# IO_BOARD_BOTTOM.net
KiCad netlist of a schematic drawn in EAGLE
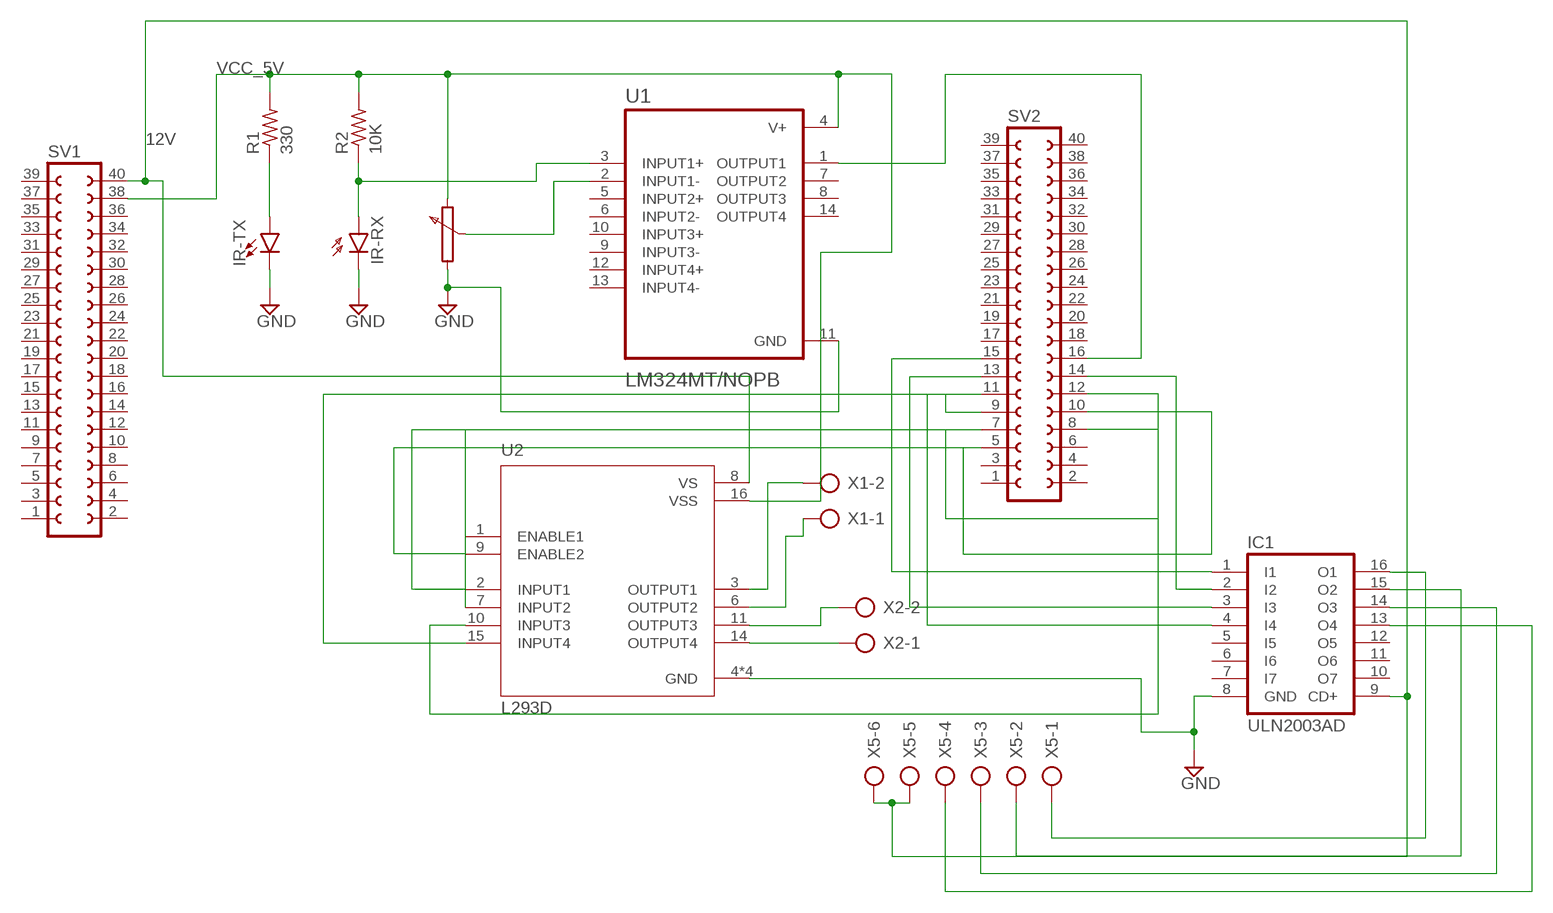
[diagram p0: schematic, sheet 1]

(export (version "E")
  (design (tool "Eeschema 10.0.6"))
  (components
    (comp (ref "IC1")
      (value "ULN2003AD")
      (footprint "eagle-import:SO16")
      (fields (field (name "MF") "STMicroelectronics") (field (name "MP") "ULN2003A"))
      (libsource (lib "eagle-import") (part "ULN2003AD"))
    )
    (comp (ref "IR-RX")
      (value "SFH205")
      (footprint "eagle-import:SFH205")
      (libsource (lib "eagle-import") (part "SFH205"))
    )
    (comp (ref "IR-TX")
      (value "LED-IRTSAL6100")
      (footprint "eagle-import:LED_5MM")
      (libsource (lib "eagle-import") (part "LED-IRTSAL6100"))
    )
    (comp (ref "R1")
      (value "330")
      (footprint "eagle-import:0204V")
      (libsource (lib "eagle-import") (part "R-US_0204/2V"))
    )
    (comp (ref "R2")
      (value "10K")
      (footprint "eagle-import:0204V")
      (libsource (lib "eagle-import") (part "R-US_0204/2V"))
    )
    (comp (ref "SV1")
      (value "FE20-2")
      (footprint "eagle-import:FE20-2")
      (libsource (lib "eagle-import") (part "FE20-2"))
    )
    (comp (ref "SV2")
      (value "FE20-2")
      (footprint "eagle-import:FE20-2")
      (libsource (lib "eagle-import") (part "FE20-2"))
    )
    (comp (ref "U1")
      (value "LM324MT/NOPB")
      (footprint "eagle-import:SOP65P640X120-14N")
      (fields (field (name "MF") "Texas Instruments") (field (name "MP") "LM324MT"))
      (libsource (lib "eagle-import") (part "LM324MT/NOPB"))
    )
    (comp (ref "U2")
      (value "L293D")
      (footprint "eagle-import:DIP880W50P254L2000H510Q16")
      (fields (field (name "MF") "STMicroelectronics"))
      (libsource (lib "eagle-import") (part "L293D"))
    )
    (comp (ref "X1")
      (value "AK500/2")
      (footprint "eagle-import:AK500_2")
      (libsource (lib "eagle-import") (part "AK500/2"))
    )
    (comp (ref "X2")
      (value "AK500/2")
      (footprint "eagle-import:AK500_2")
      (libsource (lib "eagle-import") (part "AK500/2"))
    )
    (comp (ref "X5")
      (value "AK500/6")
      (footprint "eagle-import:AK500_6")
      (libsource (lib "eagle-import") (part "AK500/6"))
    )
  )
  (nets
    (net (code "1") (name "/12V") (class "Default")
      (node (ref "IC1") (pin "9") (pinfunction "CD+_9") (pintype "passive"))
      (node (ref "SV1") (pin "40") (pinfunction "40_40") (pintype "passive"))
      (node (ref "U2") (pin "8") (pinfunction "VS_8") (pintype "power_in"))
      (node (ref "X5") (pin "5") (pinfunction "KL_5") (pintype "passive"))
      (node (ref "X5") (pin "6") (pinfunction "KL_6") (pintype "passive"))
    )
    (net (code "2") (name "/VCC_5V") (class "Default")
      (node (ref "R1") (pin "2") (pinfunction "2_2") (pintype "passive"))
      (node (ref "R2") (pin "2") (pinfunction "2_2") (pintype "passive"))
      (node (ref "SV1") (pin "38") (pinfunction "38_38") (pintype "passive"))
      (node (ref "U1") (pin "4") (pinfunction "V+_4") (pintype "power_in"))
      (node (ref "U2") (pin "16") (pinfunction "VSS_16") (pintype "power_in"))
    )
    (net (code "3") (name "GND") (class "Default")
      (node (ref "IC1") (pin "8") (pinfunction "GND_8") (pintype "power_in"))
      (node (ref "IR-RX") (pin "K") (pinfunction "C_K") (pintype "passive"))
      (node (ref "IR-TX") (pin "K") (pinfunction "C_K") (pintype "passive"))
      (node (ref "U1") (pin "11") (pinfunction "GND_11") (pintype "power_in"))
      (node (ref "U2") (pin "12") (pinfunction "GND_12") (pintype "power_in"))
      (node (ref "U2") (pin "13") (pinfunction "GND_13") (pintype "power_in"))
      (node (ref "U2") (pin "4") (pinfunction "GND_4") (pintype "power_in"))
      (node (ref "U2") (pin "5") (pinfunction "GND_5") (pintype "power_in"))
    )
    (net (code "4") (name "Net-(IC1-I1)") (class "Default")
      (node (ref "IC1") (pin "1") (pinfunction "I1_1") (pintype "input"))
      (node (ref "SV2") (pin "15") (pinfunction "15_15") (pintype "passive"))
    )
    (net (code "5") (name "Net-(IC1-I2)") (class "Default")
      (node (ref "IC1") (pin "2") (pinfunction "I2_2") (pintype "input"))
      (node (ref "SV2") (pin "14") (pinfunction "14_14") (pintype "passive"))
    )
    (net (code "6") (name "Net-(IC1-I3)") (class "Default")
      (node (ref "IC1") (pin "3") (pinfunction "I3_3") (pintype "input"))
      (node (ref "SV2") (pin "13") (pinfunction "13_13") (pintype "passive"))
    )
    (net (code "7") (name "Net-(IC1-I4)") (class "Default")
      (node (ref "IC1") (pin "4") (pinfunction "I4_4") (pintype "input"))
      (node (ref "SV2") (pin "11") (pinfunction "11_11") (pintype "passive"))
    )
    (net (code "8") (name "Net-(IC1-O1)") (class "Default")
      (node (ref "IC1") (pin "16") (pinfunction "O1_16") (pintype "open_collector"))
      (node (ref "X5") (pin "1") (pinfunction "KL_1") (pintype "passive"))
    )
    (net (code "9") (name "Net-(IC1-O2)") (class "Default")
      (node (ref "IC1") (pin "15") (pinfunction "O2_15") (pintype "open_collector"))
      (node (ref "X5") (pin "2") (pinfunction "KL_2") (pintype "passive"))
    )
    (net (code "10") (name "Net-(IC1-O3)") (class "Default")
      (node (ref "IC1") (pin "14") (pinfunction "O3_14") (pintype "open_collector"))
      (node (ref "X5") (pin "3") (pinfunction "KL_3") (pintype "passive"))
    )
    (net (code "11") (name "Net-(IC1-O4)") (class "Default")
      (node (ref "IC1") (pin "13") (pinfunction "O4_13") (pintype "open_collector"))
      (node (ref "X5") (pin "4") (pinfunction "KL_4") (pintype "passive"))
    )
    (net (code "12") (name "Net-(IR-TX-PadA)") (class "Default")
      (node (ref "IR-TX") (pin "A") (pinfunction "A_A") (pintype "passive"))
      (node (ref "R1") (pin "1") (pinfunction "1_1") (pintype "passive"))
    )
    (net (code "13") (name "Net-(U1-INPUT1+)") (class "Default")
      (node (ref "IR-RX") (pin "A") (pinfunction "A_A") (pintype "passive"))
      (node (ref "R2") (pin "1") (pinfunction "1_1") (pintype "passive"))
      (node (ref "U1") (pin "3") (pinfunction "INPUT1+_3") (pintype "input"))
    )
    (net (code "14") (name "Net-(U1-OUTPUT1)") (class "Default")
      (node (ref "SV2") (pin "16") (pinfunction "16_16") (pintype "passive"))
      (node (ref "U1") (pin "1") (pinfunction "OUTPUT1_1") (pintype "output"))
    )
    (net (code "15") (name "Net-(U2-ENABLE1)") (class "Default")
      (node (ref "SV2") (pin "8") (pinfunction "8_8") (pintype "passive"))
      (node (ref "U2") (pin "1") (pinfunction "ENABLE1_1") (pintype "input"))
    )
    (net (code "16") (name "Net-(U2-ENABLE2)") (class "Default")
      (node (ref "SV2") (pin "10") (pinfunction "10_10") (pintype "passive"))
      (node (ref "U2") (pin "9") (pinfunction "ENABLE2_9") (pintype "input"))
    )
    (net (code "17") (name "Net-(U2-INPUT1)") (class "Default")
      (node (ref "SV2") (pin "7") (pinfunction "7_7") (pintype "passive"))
      (node (ref "U2") (pin "2") (pinfunction "INPUT1_2") (pintype "input"))
    )
    (net (code "18") (name "Net-(U2-INPUT2)") (class "Default")
      (node (ref "SV2") (pin "5") (pinfunction "5_5") (pintype "passive"))
      (node (ref "U2") (pin "7") (pinfunction "INPUT2_7") (pintype "input"))
    )
    (net (code "19") (name "Net-(U2-INPUT3)") (class "Default")
      (node (ref "SV2") (pin "12") (pinfunction "12_12") (pintype "passive"))
      (node (ref "U2") (pin "10") (pinfunction "INPUT3_10") (pintype "input"))
    )
    (net (code "20") (name "Net-(U2-INPUT4)") (class "Default")
      (node (ref "SV2") (pin "9") (pinfunction "9_9") (pintype "passive"))
      (node (ref "U2") (pin "15") (pinfunction "INPUT4_15") (pintype "input"))
    )
    (net (code "21") (name "Net-(U2-OUTPUT1)") (class "Default")
      (node (ref "U2") (pin "3") (pinfunction "OUTPUT1_3") (pintype "output"))
      (node (ref "X1") (pin "2") (pinfunction "KL_2") (pintype "passive"))
    )
    (net (code "22") (name "Net-(U2-OUTPUT2)") (class "Default")
      (node (ref "U2") (pin "6") (pinfunction "OUTPUT2_6") (pintype "output"))
      (node (ref "X1") (pin "1") (pinfunction "KL_1") (pintype "passive"))
    )
    (net (code "23") (name "Net-(U2-OUTPUT3)") (class "Default")
      (node (ref "U2") (pin "11") (pinfunction "OUTPUT3_11") (pintype "output"))
      (node (ref "X2") (pin "2") (pinfunction "KL_2") (pintype "passive"))
    )
    (net (code "24") (name "Net-(U2-OUTPUT4)") (class "Default")
      (node (ref "U2") (pin "14") (pinfunction "OUTPUT4_14") (pintype "output"))
      (node (ref "X2") (pin "1") (pinfunction "KL_1") (pintype "passive"))
    )
    (net (code "25") (name "unconnected-(IC1-I5-Pad5)") (class "Default")
      (node (ref "IC1") (pin "5") (pinfunction "I5_5") (pintype "input"))
    )
    (net (code "26") (name "unconnected-(IC1-I6-Pad6)") (class "Default")
      (node (ref "IC1") (pin "6") (pinfunction "I6_6") (pintype "input"))
    )
    (net (code "27") (name "unconnected-(IC1-I7-Pad7)") (class "Default")
      (node (ref "IC1") (pin "7") (pinfunction "I7_7") (pintype "input"))
    )
    (net (code "28") (name "unconnected-(IC1-O5-Pad12)") (class "Default")
      (node (ref "IC1") (pin "12") (pinfunction "O5_12") (pintype "open_collector"))
    )
    (net (code "29") (name "unconnected-(IC1-O6-Pad11)") (class "Default")
      (node (ref "IC1") (pin "11") (pinfunction "O6_11") (pintype "open_collector"))
    )
    (net (code "30") (name "unconnected-(IC1-O7-Pad10)") (class "Default")
      (node (ref "IC1") (pin "10") (pinfunction "O7_10") (pintype "open_collector"))
    )
    (net (code "31") (name "unconnected-(SV1-Pad1)") (class "Default")
      (node (ref "SV1") (pin "1") (pinfunction "1_1") (pintype "passive"))
    )
    (net (code "32") (name "unconnected-(SV1-Pad2)") (class "Default")
      (node (ref "SV1") (pin "2") (pinfunction "2_2") (pintype "passive"))
    )
    (net (code "33") (name "unconnected-(SV1-Pad3)") (class "Default")
      (node (ref "SV1") (pin "3") (pinfunction "3_3") (pintype "passive"))
    )
    (net (code "34") (name "unconnected-(SV1-Pad4)") (class "Default")
      (node (ref "SV1") (pin "4") (pinfunction "4_4") (pintype "passive"))
    )
    (net (code "35") (name "unconnected-(SV1-Pad5)") (class "Default")
      (node (ref "SV1") (pin "5") (pinfunction "5_5") (pintype "passive"))
    )
    (net (code "36") (name "unconnected-(SV1-Pad6)") (class "Default")
      (node (ref "SV1") (pin "6") (pinfunction "6_6") (pintype "passive"))
    )
    (net (code "37") (name "unconnected-(SV1-Pad7)") (class "Default")
      (node (ref "SV1") (pin "7") (pinfunction "7_7") (pintype "passive"))
    )
    (net (code "38") (name "unconnected-(SV1-Pad8)") (class "Default")
      (node (ref "SV1") (pin "8") (pinfunction "8_8") (pintype "passive"))
    )
    (net (code "39") (name "unconnected-(SV1-Pad9)") (class "Default")
      (node (ref "SV1") (pin "9") (pinfunction "9_9") (pintype "passive"))
    )
    (net (code "40") (name "unconnected-(SV1-Pad10)") (class "Default")
      (node (ref "SV1") (pin "10") (pinfunction "10_10") (pintype "passive"))
    )
    (net (code "41") (name "unconnected-(SV1-Pad11)") (class "Default")
      (node (ref "SV1") (pin "11") (pinfunction "11_11") (pintype "passive"))
    )
    (net (code "42") (name "unconnected-(SV1-Pad12)") (class "Default")
      (node (ref "SV1") (pin "12") (pinfunction "12_12") (pintype "passive"))
    )
    (net (code "43") (name "unconnected-(SV1-Pad13)") (class "Default")
      (node (ref "SV1") (pin "13") (pinfunction "13_13") (pintype "passive"))
    )
    (net (code "44") (name "unconnected-(SV1-Pad14)") (class "Default")
      (node (ref "SV1") (pin "14") (pinfunction "14_14") (pintype "passive"))
    )
    (net (code "45") (name "unconnected-(SV1-Pad15)") (class "Default")
      (node (ref "SV1") (pin "15") (pinfunction "15_15") (pintype "passive"))
    )
    (net (code "46") (name "unconnected-(SV1-Pad16)") (class "Default")
      (node (ref "SV1") (pin "16") (pinfunction "16_16") (pintype "passive"))
    )
    (net (code "47") (name "unconnected-(SV1-Pad17)") (class "Default")
      (node (ref "SV1") (pin "17") (pinfunction "17_17") (pintype "passive"))
    )
    (net (code "48") (name "unconnected-(SV1-Pad18)") (class "Default")
      (node (ref "SV1") (pin "18") (pinfunction "18_18") (pintype "passive"))
    )
    (net (code "49") (name "unconnected-(SV1-Pad19)") (class "Default")
      (node (ref "SV1") (pin "19") (pinfunction "19_19") (pintype "passive"))
    )
    (net (code "50") (name "unconnected-(SV1-Pad20)") (class "Default")
      (node (ref "SV1") (pin "20") (pinfunction "20_20") (pintype "passive"))
    )
    (net (code "51") (name "unconnected-(SV1-Pad21)") (class "Default")
      (node (ref "SV1") (pin "21") (pinfunction "21_21") (pintype "passive"))
    )
    (net (code "52") (name "unconnected-(SV1-Pad22)") (class "Default")
      (node (ref "SV1") (pin "22") (pinfunction "22_22") (pintype "passive"))
    )
    (net (code "53") (name "unconnected-(SV1-Pad23)") (class "Default")
      (node (ref "SV1") (pin "23") (pinfunction "23_23") (pintype "passive"))
    )
    (net (code "54") (name "unconnected-(SV1-Pad24)") (class "Default")
      (node (ref "SV1") (pin "24") (pinfunction "24_24") (pintype "passive"))
    )
    (net (code "55") (name "unconnected-(SV1-Pad25)") (class "Default")
      (node (ref "SV1") (pin "25") (pinfunction "25_25") (pintype "passive"))
    )
    (net (code "56") (name "unconnected-(SV1-Pad26)") (class "Default")
      (node (ref "SV1") (pin "26") (pinfunction "26_26") (pintype "passive"))
    )
    (net (code "57") (name "unconnected-(SV1-Pad27)") (class "Default")
      (node (ref "SV1") (pin "27") (pinfunction "27_27") (pintype "passive"))
    )
    (net (code "58") (name "unconnected-(SV1-Pad28)") (class "Default")
      (node (ref "SV1") (pin "28") (pinfunction "28_28") (pintype "passive"))
    )
    (net (code "59") (name "unconnected-(SV1-Pad29)") (class "Default")
      (node (ref "SV1") (pin "29") (pinfunction "29_29") (pintype "passive"))
    )
    (net (code "60") (name "unconnected-(SV1-Pad30)") (class "Default")
      (node (ref "SV1") (pin "30") (pinfunction "30_30") (pintype "passive"))
    )
    (net (code "61") (name "unconnected-(SV1-Pad31)") (class "Default")
      (node (ref "SV1") (pin "31") (pinfunction "31_31") (pintype "passive"))
    )
    (net (code "62") (name "unconnected-(SV1-Pad32)") (class "Default")
      (node (ref "SV1") (pin "32") (pinfunction "32_32") (pintype "passive"))
    )
    (net (code "63") (name "unconnected-(SV1-Pad33)") (class "Default")
      (node (ref "SV1") (pin "33") (pinfunction "33_33") (pintype "passive"))
    )
    (net (code "64") (name "unconnected-(SV1-Pad34)") (class "Default")
      (node (ref "SV1") (pin "34") (pinfunction "34_34") (pintype "passive"))
    )
    (net (code "65") (name "unconnected-(SV1-Pad35)") (class "Default")
      (node (ref "SV1") (pin "35") (pinfunction "35_35") (pintype "passive"))
    )
    (net (code "66") (name "unconnected-(SV1-Pad36)") (class "Default")
      (node (ref "SV1") (pin "36") (pinfunction "36_36") (pintype "passive"))
    )
    (net (code "67") (name "unconnected-(SV1-Pad37)") (class "Default")
      (node (ref "SV1") (pin "37") (pinfunction "37_37") (pintype "passive"))
    )
    (net (code "68") (name "unconnected-(SV1-Pad39)") (class "Default")
      (node (ref "SV1") (pin "39") (pinfunction "39_39") (pintype "passive"))
    )
    (net (code "69") (name "unconnected-(SV2-Pad1)") (class "Default")
      (node (ref "SV2") (pin "1") (pinfunction "1_1") (pintype "passive"))
    )
    (net (code "70") (name "unconnected-(SV2-Pad2)") (class "Default")
      (node (ref "SV2") (pin "2") (pinfunction "2_2") (pintype "passive"))
    )
    (net (code "71") (name "unconnected-(SV2-Pad3)") (class "Default")
      (node (ref "SV2") (pin "3") (pinfunction "3_3") (pintype "passive"))
    )
    (net (code "72") (name "unconnected-(SV2-Pad4)") (class "Default")
      (node (ref "SV2") (pin "4") (pinfunction "4_4") (pintype "passive"))
    )
    (net (code "73") (name "unconnected-(SV2-Pad6)") (class "Default")
      (node (ref "SV2") (pin "6") (pinfunction "6_6") (pintype "passive"))
    )
    (net (code "74") (name "unconnected-(SV2-Pad17)") (class "Default")
      (node (ref "SV2") (pin "17") (pinfunction "17_17") (pintype "passive"))
    )
    (net (code "75") (name "unconnected-(SV2-Pad18)") (class "Default")
      (node (ref "SV2") (pin "18") (pinfunction "18_18") (pintype "passive"))
    )
    (net (code "76") (name "unconnected-(SV2-Pad19)") (class "Default")
      (node (ref "SV2") (pin "19") (pinfunction "19_19") (pintype "passive"))
    )
    (net (code "77") (name "unconnected-(SV2-Pad20)") (class "Default")
      (node (ref "SV2") (pin "20") (pinfunction "20_20") (pintype "passive"))
    )
    (net (code "78") (name "unconnected-(SV2-Pad21)") (class "Default")
      (node (ref "SV2") (pin "21") (pinfunction "21_21") (pintype "passive"))
    )
    (net (code "79") (name "unconnected-(SV2-Pad22)") (class "Default")
      (node (ref "SV2") (pin "22") (pinfunction "22_22") (pintype "passive"))
    )
    (net (code "80") (name "unconnected-(SV2-Pad23)") (class "Default")
      (node (ref "SV2") (pin "23") (pinfunction "23_23") (pintype "passive"))
    )
    (net (code "81") (name "unconnected-(SV2-Pad24)") (class "Default")
      (node (ref "SV2") (pin "24") (pinfunction "24_24") (pintype "passive"))
    )
    (net (code "82") (name "unconnected-(SV2-Pad25)") (class "Default")
      (node (ref "SV2") (pin "25") (pinfunction "25_25") (pintype "passive"))
    )
    (net (code "83") (name "unconnected-(SV2-Pad26)") (class "Default")
      (node (ref "SV2") (pin "26") (pinfunction "26_26") (pintype "passive"))
    )
    (net (code "84") (name "unconnected-(SV2-Pad27)") (class "Default")
      (node (ref "SV2") (pin "27") (pinfunction "27_27") (pintype "passive"))
    )
    (net (code "85") (name "unconnected-(SV2-Pad28)") (class "Default")
      (node (ref "SV2") (pin "28") (pinfunction "28_28") (pintype "passive"))
    )
    (net (code "86") (name "unconnected-(SV2-Pad29)") (class "Default")
      (node (ref "SV2") (pin "29") (pinfunction "29_29") (pintype "passive"))
    )
    (net (code "87") (name "unconnected-(SV2-Pad30)") (class "Default")
      (node (ref "SV2") (pin "30") (pinfunction "30_30") (pintype "passive"))
    )
    (net (code "88") (name "unconnected-(SV2-Pad31)") (class "Default")
      (node (ref "SV2") (pin "31") (pinfunction "31_31") (pintype "passive"))
    )
    (net (code "89") (name "unconnected-(SV2-Pad32)") (class "Default")
      (node (ref "SV2") (pin "32") (pinfunction "32_32") (pintype "passive"))
    )
    (net (code "90") (name "unconnected-(SV2-Pad33)") (class "Default")
      (node (ref "SV2") (pin "33") (pinfunction "33_33") (pintype "passive"))
    )
    (net (code "91") (name "unconnected-(SV2-Pad34)") (class "Default")
      (node (ref "SV2") (pin "34") (pinfunction "34_34") (pintype "passive"))
    )
    (net (code "92") (name "unconnected-(SV2-Pad35)") (class "Default")
      (node (ref "SV2") (pin "35") (pinfunction "35_35") (pintype "passive"))
    )
    (net (code "93") (name "unconnected-(SV2-Pad36)") (class "Default")
      (node (ref "SV2") (pin "36") (pinfunction "36_36") (pintype "passive"))
    )
    (net (code "94") (name "unconnected-(SV2-Pad37)") (class "Default")
      (node (ref "SV2") (pin "37") (pinfunction "37_37") (pintype "passive"))
    )
    (net (code "95") (name "unconnected-(SV2-Pad38)") (class "Default")
      (node (ref "SV2") (pin "38") (pinfunction "38_38") (pintype "passive"))
    )
    (net (code "96") (name "unconnected-(SV2-Pad39)") (class "Default")
      (node (ref "SV2") (pin "39") (pinfunction "39_39") (pintype "passive"))
    )
    (net (code "97") (name "unconnected-(SV2-Pad40)") (class "Default")
      (node (ref "SV2") (pin "40") (pinfunction "40_40") (pintype "passive"))
    )
    (net (code "98") (name "unconnected-(U1-INPUT1--Pad2)") (class "Default")
      (node (ref "U1") (pin "2") (pinfunction "INPUT1-_2") (pintype "input"))
    )
    (net (code "99") (name "unconnected-(U1-INPUT2+-Pad5)") (class "Default")
      (node (ref "U1") (pin "5") (pinfunction "INPUT2+_5") (pintype "input"))
    )
    (net (code "100") (name "unconnected-(U1-INPUT2--Pad6)") (class "Default")
      (node (ref "U1") (pin "6") (pinfunction "INPUT2-_6") (pintype "input"))
    )
    (net (code "101") (name "unconnected-(U1-INPUT3+-Pad10)") (class "Default")
      (node (ref "U1") (pin "10") (pinfunction "INPUT3+_10") (pintype "input"))
    )
    (net (code "102") (name "unconnected-(U1-INPUT3--Pad9)") (class "Default")
      (node (ref "U1") (pin "9") (pinfunction "INPUT3-_9") (pintype "input"))
    )
    (net (code "103") (name "unconnected-(U1-INPUT4+-Pad12)") (class "Default")
      (node (ref "U1") (pin "12") (pinfunction "INPUT4+_12") (pintype "input"))
    )
    (net (code "104") (name "unconnected-(U1-INPUT4--Pad13)") (class "Default")
      (node (ref "U1") (pin "13") (pinfunction "INPUT4-_13") (pintype "input"))
    )
    (net (code "105") (name "unconnected-(U1-OUTPUT2-Pad7)") (class "Default")
      (node (ref "U1") (pin "7") (pinfunction "OUTPUT2_7") (pintype "output"))
    )
    (net (code "106") (name "unconnected-(U1-OUTPUT3-Pad8)") (class "Default")
      (node (ref "U1") (pin "8") (pinfunction "OUTPUT3_8") (pintype "output"))
    )
    (net (code "107") (name "unconnected-(U1-OUTPUT4-Pad14)") (class "Default")
      (node (ref "U1") (pin "14") (pinfunction "OUTPUT4_14") (pintype "output"))
    )
  )
)
